# 2014_MiniYaourtPhone.net
KiCad netlist of a schematic drawn in Altium Designer
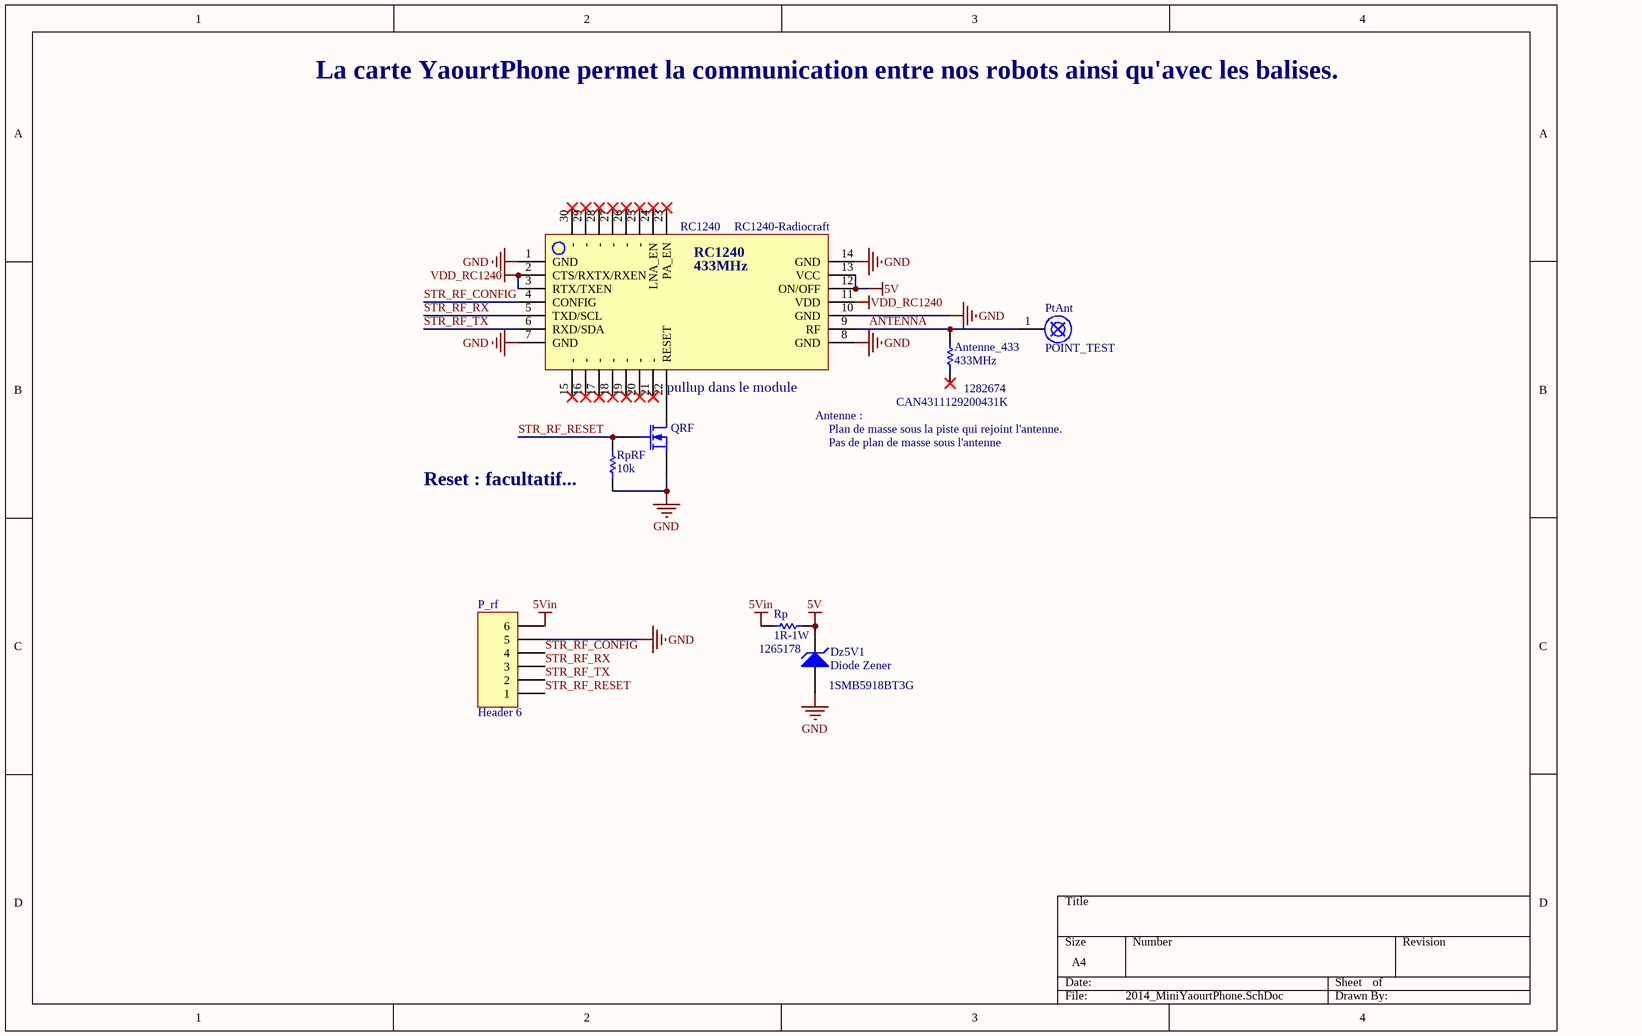
[diagram p0: 2014_MiniYaourtPhone.SchDoc]

(export (version "E")
  (design (tool "Eeschema 10.0.6"))
  (components
    (comp (ref "Antenne_433")
      (value "433MHz")
      (footprint "R1206_N")
      (description "CAN4311129200431K")
      (fields
        (field (name "PACKAGEREFERENCE") "CAN4311129200431K")
        (field (name "FAR") "1282674")
        (field (name "PUBLISHER") "Altium Limited")
      )
      (libsource (lib "_ROBOT") (part "Resistor"))
    )
    (comp (ref "Dz5V1")
      (value "Diode Zener")
      (footprint "DIODE_CMS_SMB")
      (description "Zener Diode")
      (fields (field (name "ALTIUM_UNNAMED_1") "1SMB5918BT3G"))
      (libsource (lib "_ROBOT") (part "Diode Zener"))
    )
    (comp (ref "PtAnt")
      (value "POINT_TEST")
      (footprint "POINT_TEST")
      (description "POINT TEST")
      (libsource (lib "connecteurs") (part "POINT_TEST"))
    )
    (comp (ref "P_rf")
      (value "Header 6")
      (footprint "HDR1X6")
      (description "Header, 6-Pin")
      (fields (field (name "PUBLISHER") "Altium Limited"))
      (libsource (lib "DG_Connecteur") (part "Header 6"))
    )
    (comp (ref "QRF")
      (value "Transistor MOSFET-N")
      (footprint "SOT23-3N")
      (description "N-Channel MOSFET")
      (fields (field (name "PUBLISHER") "Altium Limited"))
      (libsource (lib "_ROBOT") (part "Transistor MOSFET-N"))
    )
    (comp (ref "RC1240")
      (value "RC1240-Radiocraft")
      (footprint "RC1240")
      (description "RC1240 - Radiocraft 433MHz Transceiver")
      (libsource (lib "_ROBOT") (part "RC1240-Radiocraft"))
    )
    (comp (ref "Rp")
      (value "1R-1W")
      (footprint "INDUCTANCE_CMS_1812")
      (description "Resistor")
      (fields (field (name "FAR") "1265178") (field (name "PUBLISHER") "Altium Limited"))
      (libsource (lib "_ROBOT") (part "Resistor"))
    )
    (comp (ref "RpRF")
      (value "10k")
      (footprint "R1206_N")
      (description "Resistor")
      (fields (field (name "PUBLISHER") "Altium Limited"))
      (libsource (lib "_ROBOT") (part "Resistor"))
    )
  )
  (nets
    (net (code "1") (name "/ANTENNA") (class "Default")
      (node (ref "Antenne_433") (pin "1") (pinfunction "1_1") (pintype "passive"))
      (node (ref "PtAnt") (pin "1") (pinfunction "3_1") (pintype "passive"))
      (node (ref "RC1240") (pin "9") (pinfunction "RF_9") (pintype "passive"))
    )
    (net (code "2") (name "/STR_RF_CONFIG") (class "Default")
      (node (ref "P_rf") (pin "4") (pinfunction "4_4") (pintype "passive"))
      (node (ref "RC1240") (pin "4") (pinfunction "CONFIG_4") (pintype "passive"))
    )
    (net (code "3") (name "/STR_RF_RESET") (class "Default")
      (node (ref "P_rf") (pin "1") (pinfunction "1_1") (pintype "passive"))
      (node (ref "QRF") (pin "1") (pinfunction "G_1") (pintype "passive"))
      (node (ref "RpRF") (pin "1") (pinfunction "1_1") (pintype "passive"))
    )
    (net (code "4") (name "/STR_RF_RX") (class "Default")
      (node (ref "P_rf") (pin "3") (pinfunction "3_3") (pintype "passive"))
      (node (ref "RC1240") (pin "5") (pinfunction "TXD/SCL_5") (pintype "passive"))
    )
    (net (code "5") (name "/STR_RF_TX") (class "Default")
      (node (ref "P_rf") (pin "2") (pinfunction "2_2") (pintype "passive"))
      (node (ref "RC1240") (pin "6") (pinfunction "RXD/SDA_6") (pintype "passive"))
    )
    (net (code "6") (name "5V") (class "Default")
      (node (ref "Dz5V1") (pin "2") (pinfunction "K_2") (pintype "passive"))
      (node (ref "RC1240") (pin "12") (pinfunction "ON/OFF_12") (pintype "passive"))
      (node (ref "RC1240") (pin "13") (pinfunction "VCC_13") (pintype "passive"))
      (node (ref "Rp") (pin "2") (pinfunction "2_2") (pintype "passive"))
    )
    (net (code "7") (name "5Vin") (class "Default")
      (node (ref "P_rf") (pin "6") (pinfunction "6_6") (pintype "passive"))
      (node (ref "Rp") (pin "1") (pinfunction "1_1") (pintype "passive"))
    )
    (net (code "8") (name "GND") (class "Default")
      (node (ref "Dz5V1") (pin "1") (pinfunction "A_1") (pintype "passive"))
      (node (ref "P_rf") (pin "5") (pinfunction "5_5") (pintype "passive"))
      (node (ref "QRF") (pin "2") (pinfunction "S_2") (pintype "passive"))
      (node (ref "RC1240") (pin "1") (pinfunction "GND_1") (pintype "passive"))
      (node (ref "RC1240") (pin "10") (pinfunction "GND_10") (pintype "passive"))
      (node (ref "RC1240") (pin "14") (pinfunction "GND_14") (pintype "passive"))
      (node (ref "RC1240") (pin "7") (pinfunction "GND_7") (pintype "passive"))
      (node (ref "RC1240") (pin "8") (pinfunction "GND_8") (pintype "passive"))
      (node (ref "RpRF") (pin "2") (pinfunction "2_2") (pintype "passive"))
    )
    (net (code "9") (name "Net-(QRF-D)") (class "Default")
      (node (ref "QRF") (pin "3") (pinfunction "D_3") (pintype "passive"))
      (node (ref "RC1240") (pin "22") (pinfunction "RESET_22") (pintype "passive"))
    )
    (net (code "10") (name "VDD_RC1240") (class "Default")
      (node (ref "RC1240") (pin "11") (pinfunction "VDD_11") (pintype "passive"))
      (node (ref "RC1240") (pin "2") (pinfunction "CTS/RXTX/RXEN_2") (pintype "passive"))
      (node (ref "RC1240") (pin "3") (pinfunction "RTX/TXEN_3") (pintype "passive"))
    )
    (net (code "11") (name "unconnected-(Antenne_433-Pad2)") (class "Default")
      (node (ref "Antenne_433") (pin "2") (pinfunction "2_2") (pintype "passive+no_connect"))
    )
    (net (code "12") (name "unconnected-(RC1240---Pad15)") (class "Default")
      (node (ref "RC1240") (pin "15") (pinfunction "-_15") (pintype "passive+no_connect"))
    )
    (net (code "13") (name "unconnected-(RC1240---Pad16)") (class "Default")
      (node (ref "RC1240") (pin "16") (pinfunction "-_16") (pintype "passive+no_connect"))
    )
    (net (code "14") (name "unconnected-(RC1240---Pad17)") (class "Default")
      (node (ref "RC1240") (pin "17") (pinfunction "-_17") (pintype "passive+no_connect"))
    )
    (net (code "15") (name "unconnected-(RC1240---Pad18)") (class "Default")
      (node (ref "RC1240") (pin "18") (pinfunction "-_18") (pintype "passive+no_connect"))
    )
    (net (code "16") (name "unconnected-(RC1240---Pad19)") (class "Default")
      (node (ref "RC1240") (pin "19") (pinfunction "-_19") (pintype "passive+no_connect"))
    )
    (net (code "17") (name "unconnected-(RC1240---Pad20)") (class "Default")
      (node (ref "RC1240") (pin "20") (pinfunction "-_20") (pintype "passive+no_connect"))
    )
    (net (code "18") (name "unconnected-(RC1240---Pad21)") (class "Default")
      (node (ref "RC1240") (pin "21") (pinfunction "-_21") (pintype "passive+no_connect"))
    )
    (net (code "19") (name "unconnected-(RC1240---Pad25)") (class "Default")
      (node (ref "RC1240") (pin "25") (pinfunction "-_25") (pintype "passive+no_connect"))
    )
    (net (code "20") (name "unconnected-(RC1240---Pad26)") (class "Default")
      (node (ref "RC1240") (pin "26") (pinfunction "-_26") (pintype "passive+no_connect"))
    )
    (net (code "21") (name "unconnected-(RC1240---Pad27)") (class "Default")
      (node (ref "RC1240") (pin "27") (pinfunction "-_27") (pintype "passive+no_connect"))
    )
    (net (code "22") (name "unconnected-(RC1240---Pad28)") (class "Default")
      (node (ref "RC1240") (pin "28") (pinfunction "-_28") (pintype "passive+no_connect"))
    )
    (net (code "23") (name "unconnected-(RC1240---Pad29)") (class "Default")
      (node (ref "RC1240") (pin "29") (pinfunction "-_29") (pintype "passive+no_connect"))
    )
    (net (code "24") (name "unconnected-(RC1240---Pad30)") (class "Default")
      (node (ref "RC1240") (pin "30") (pinfunction "-_30") (pintype "passive+no_connect"))
    )
    (net (code "25") (name "unconnected-(RC1240-LNA_EN-Pad24)") (class "Default")
      (node (ref "RC1240") (pin "24") (pinfunction "LNA_EN_24") (pintype "passive+no_connect"))
    )
    (net (code "26") (name "unconnected-(RC1240-PA_EN-Pad23)") (class "Default")
      (node (ref "RC1240") (pin "23") (pinfunction "PA_EN_23") (pintype "passive+no_connect"))
    )
  )
)
